# Pure_SH.net
KiCad netlist of a schematic drawn in EAGLE
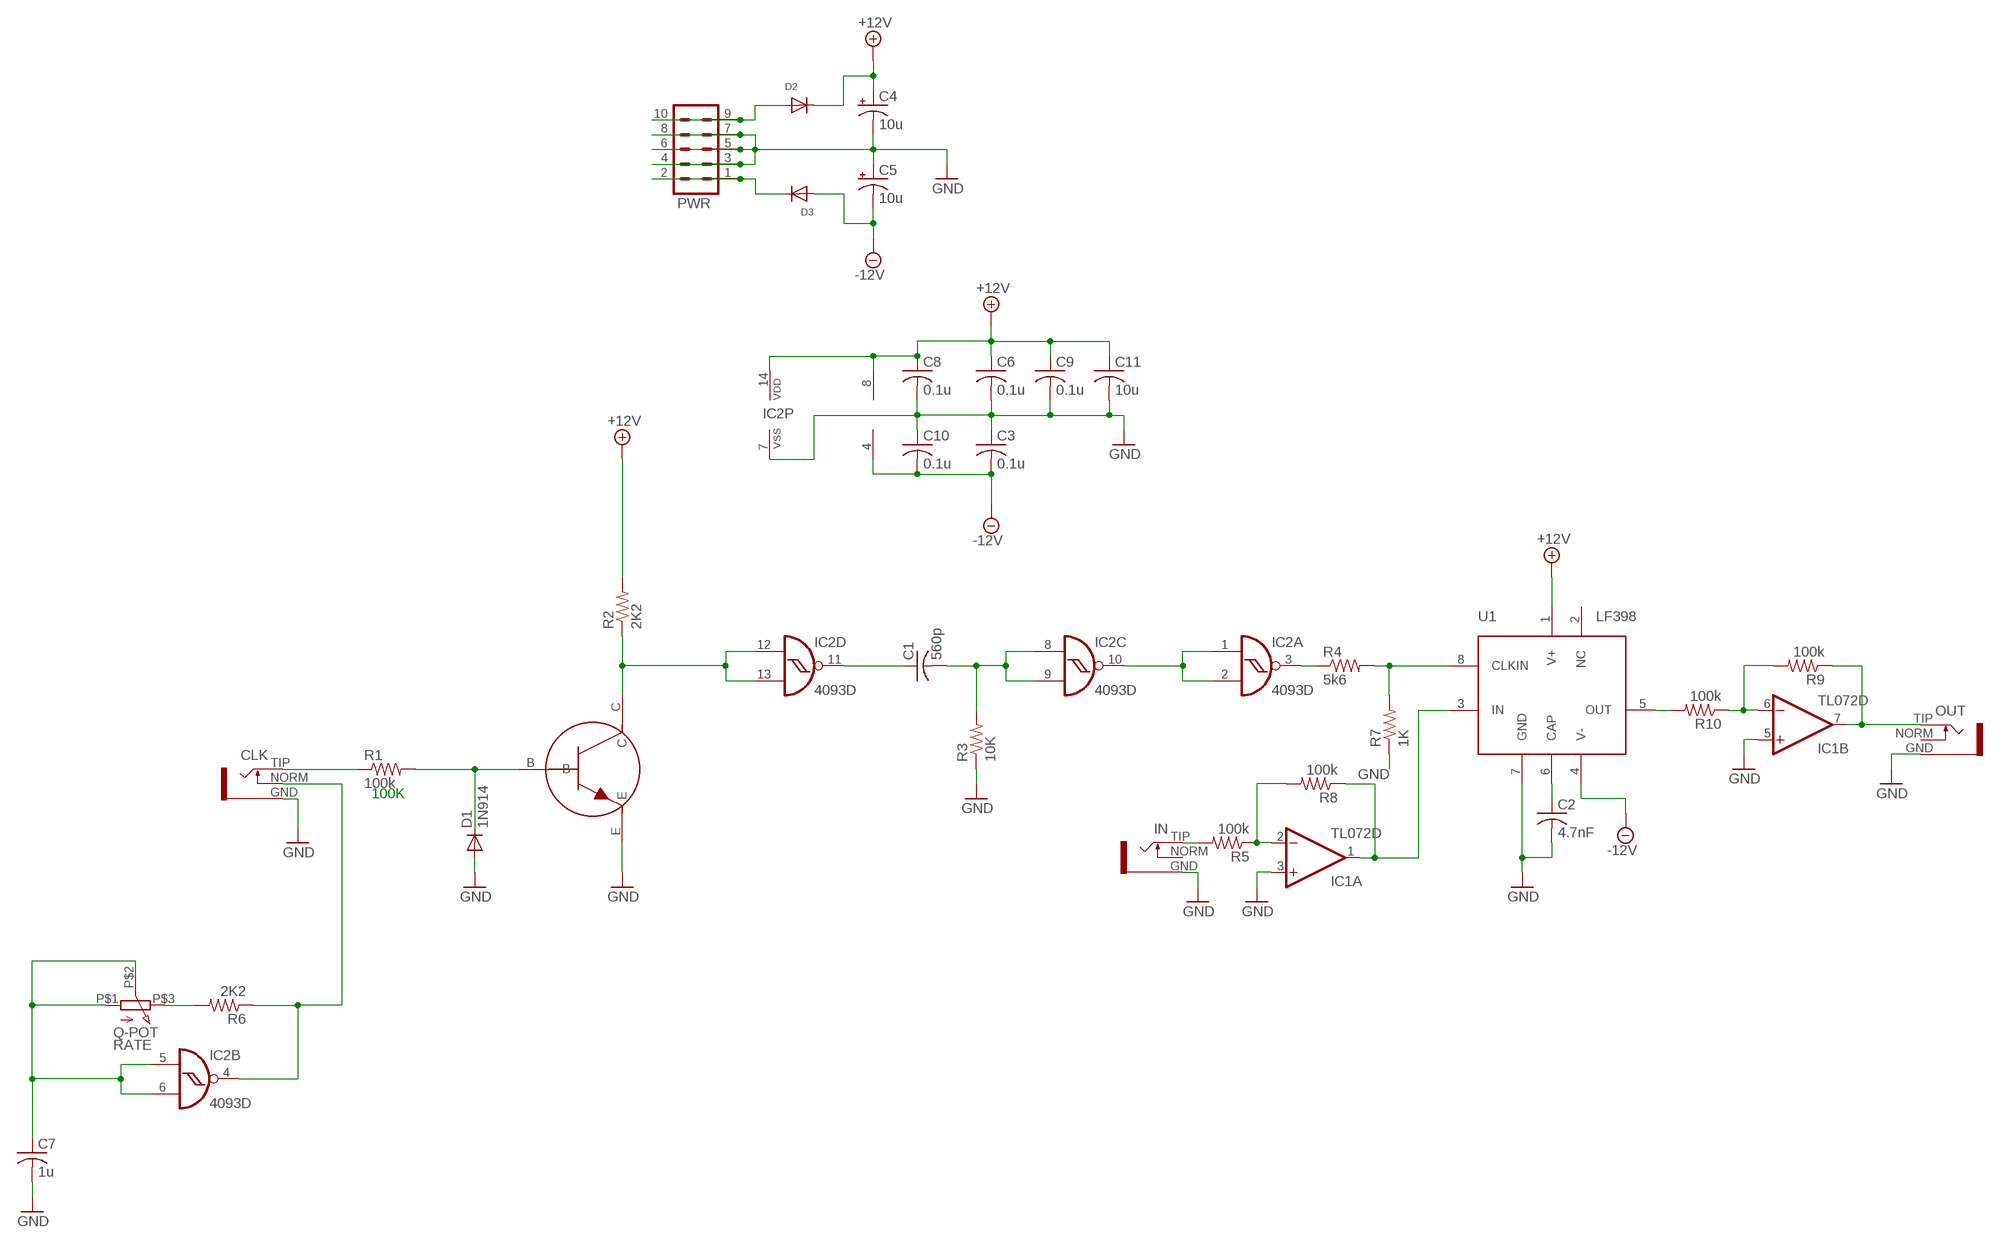
[diagram p0: schematic, sheet 1]

(export (version "E")
  (design (tool "Eeschema 10.0.6"))
  (components
    (comp (ref "C1")
      (value "560p")
      (footprint "eagle-import:C0805K")
      (libsource (lib "eagle-import") (part "C-USC0805K"))
    )
    (comp (ref "C2")
      (value "4.7nF")
      (footprint "eagle-import:C050-045X075")
      (libsource (lib "eagle-import") (part "C-US050-045X075"))
    )
    (comp (ref "C3")
      (value "0.1u")
      (footprint "eagle-import:C0805K")
      (libsource (lib "eagle-import") (part "C-USC0805K"))
    )
    (comp (ref "C4")
      (value "10u")
      (footprint "eagle-import:153CLV-0505")
      (libsource (lib "eagle-import") (part "CPOL-US153CLV-0505"))
    )
    (comp (ref "C5")
      (value "10u")
      (footprint "eagle-import:153CLV-0505")
      (libsource (lib "eagle-import") (part "CPOL-US153CLV-0505"))
    )
    (comp (ref "C6")
      (value "0.1u")
      (footprint "eagle-import:C0805K")
      (libsource (lib "eagle-import") (part "C-USC0805K"))
    )
    (comp (ref "C7")
      (value "1u")
      (footprint "eagle-import:C0805K")
      (libsource (lib "eagle-import") (part "C-USC0805K"))
    )
    (comp (ref "C8")
      (value "0.1u")
      (footprint "eagle-import:C0805K")
      (libsource (lib "eagle-import") (part "C-USC0805K"))
    )
    (comp (ref "C9")
      (value "0.1u")
      (footprint "eagle-import:C0805K")
      (libsource (lib "eagle-import") (part "C-USC0805K"))
    )
    (comp (ref "C10")
      (value "0.1u")
      (footprint "eagle-import:C0805K")
      (libsource (lib "eagle-import") (part "C-USC0805K"))
    )
    (comp (ref "C11")
      (value "10u")
      (footprint "eagle-import:C0805K")
      (libsource (lib "eagle-import") (part "C-USC0805K"))
    )
    (comp (ref "CLK")
      (value "S_JACK")
      (footprint "eagle-import:S_JACK")
      (libsource (lib "eagle-import") (part "S_JACK"))
    )
    (comp (ref "D1")
      (value "1N914")
      (footprint "eagle-import:SOD-323")
      (libsource (lib "eagle-import") (part "DIODESOD"))
    )
    (comp (ref "D2")
      (value "DIODESMA")
      (footprint "eagle-import:SMADIODE")
      (libsource (lib "eagle-import") (part "adafruit_DIODESMA"))
    )
    (comp (ref "D3")
      (value "DIODESMA")
      (footprint "eagle-import:SMADIODE")
      (libsource (lib "eagle-import") (part "adafruit_DIODESMA"))
    )
    (comp (ref "IC1")
      (value "TL072D")
      (footprint "eagle-import:SO08")
      (libsource (lib "eagle-import") (part "TL072D"))
    )
    (comp (ref "IC2")
      (value "4093D")
      (footprint "eagle-import:SO14")
      (libsource (lib "eagle-import") (part "4093D"))
    )
    (comp (ref "IN")
      (value "S_JACK")
      (footprint "eagle-import:S_JACK")
      (libsource (lib "eagle-import") (part "S_JACK"))
    )
    (comp (ref "OUT")
      (value "S_JACK")
      (footprint "eagle-import:S_JACK")
      (libsource (lib "eagle-import") (part "S_JACK"))
    )
    (comp (ref "PWR")
      (value "M05X2SHD")
      (footprint "eagle-import:2X5-SHROUDED")
      (libsource (lib "eagle-import") (part "M05X2SHD"))
    )
    (comp (ref "R1")
      (value "100k")
      (footprint "eagle-import:R0805")
      (libsource (lib "eagle-import") (part "R-US_R0805"))
    )
    (comp (ref "R2")
      (value "2K2")
      (footprint "eagle-import:R0805")
      (libsource (lib "eagle-import") (part "R-US_R0805"))
    )
    (comp (ref "R3")
      (value "10K")
      (footprint "eagle-import:R0805")
      (libsource (lib "eagle-import") (part "R-US_R0805"))
    )
    (comp (ref "R4")
      (value "5k6")
      (footprint "eagle-import:R0805")
      (libsource (lib "eagle-import") (part "R-US_R0805"))
    )
    (comp (ref "R5")
      (value "100k")
      (footprint "eagle-import:R0805")
      (libsource (lib "eagle-import") (part "R-US_R0805"))
    )
    (comp (ref "R6")
      (value "2K2")
      (footprint "eagle-import:R0805")
      (libsource (lib "eagle-import") (part "R-US_R0805"))
    )
    (comp (ref "R7")
      (value "1K")
      (footprint "eagle-import:R0805")
      (libsource (lib "eagle-import") (part "R-US_R0805"))
    )
    (comp (ref "R8")
      (value "100k")
      (footprint "eagle-import:R0805")
      (libsource (lib "eagle-import") (part "R-US_R0805"))
    )
    (comp (ref "R9")
      (value "100k")
      (footprint "eagle-import:R0805")
      (libsource (lib "eagle-import") (part "R-US_R0805"))
    )
    (comp (ref "R10")
      (value "100k")
      (footprint "eagle-import:R0805")
      (libsource (lib "eagle-import") (part "R-US_R0805"))
    )
    (comp (ref "RATE")
      (value "Q-POT")
      (footprint "eagle-import:Q-POT")
      (libsource (lib "eagle-import") (part "Q-POT"))
    )
    (comp (ref "T1")
      (value "3904")
      (footprint "eagle-import:TRANSISTOR_SINGLE_N-TYPE")
      (libsource (lib "eagle-import") (part "TRANSISTOR_MMBT3904"))
    )
    (comp (ref "U1")
      (value "LF398")
      (footprint "eagle-import:SOIC--8")
      (libsource (lib "eagle-import") (part "LF398"))
    )
  )
  (nets
    (net (code "1") (name "+12V") (class "Default")
      (node (ref "C11") (pin "1") (pinfunction "1_1") (pintype "passive"))
      (node (ref "C4") (pin "+") (pinfunction "+_+") (pintype "passive"))
      (node (ref "C6") (pin "1") (pinfunction "1_1") (pintype "passive"))
      (node (ref "C8") (pin "1") (pinfunction "1_1") (pintype "passive"))
      (node (ref "C9") (pin "1") (pinfunction "1_1") (pintype "passive"))
      (node (ref "D2") (pin "C") (pinfunction "C_C") (pintype "passive"))
      (node (ref "IC1") (pin "8") (pinfunction "V+_8") (pintype "power_in"))
      (node (ref "IC2") (pin "14") (pinfunction "VDD_14") (pintype "power_in"))
      (node (ref "R2") (pin "2") (pinfunction "2_2") (pintype "passive"))
      (node (ref "U1") (pin "1") (pinfunction "V+_1") (pintype "bidirectional"))
    )
    (net (code "2") (name "-12V") (class "Default")
      (node (ref "C10") (pin "2") (pinfunction "2_2") (pintype "passive"))
      (node (ref "C3") (pin "2") (pinfunction "2_2") (pintype "passive"))
      (node (ref "C5") (pin "-") (pinfunction "-_-") (pintype "passive"))
      (node (ref "D3") (pin "A") (pinfunction "A_A") (pintype "passive"))
      (node (ref "IC1") (pin "4") (pinfunction "V-_4") (pintype "power_in"))
      (node (ref "U1") (pin "4") (pinfunction "V-_4") (pintype "bidirectional"))
    )
    (net (code "3") (name "GND") (class "Default")
      (node (ref "C10") (pin "1") (pinfunction "1_1") (pintype "passive"))
      (node (ref "C11") (pin "2") (pinfunction "2_2") (pintype "passive"))
      (node (ref "C2") (pin "2") (pinfunction "2_2") (pintype "passive"))
      (node (ref "C3") (pin "1") (pinfunction "1_1") (pintype "passive"))
      (node (ref "C4") (pin "-") (pinfunction "-_-") (pintype "passive"))
      (node (ref "C5") (pin "+") (pinfunction "+_+") (pintype "passive"))
      (node (ref "C6") (pin "2") (pinfunction "2_2") (pintype "passive"))
      (node (ref "C7") (pin "2") (pinfunction "2_2") (pintype "passive"))
      (node (ref "C8") (pin "2") (pinfunction "2_2") (pintype "passive"))
      (node (ref "C9") (pin "2") (pinfunction "2_2") (pintype "passive"))
      (node (ref "CLK") (pin "GND") (pinfunction "GND_GND") (pintype "passive"))
      (node (ref "D1") (pin "2") (pinfunction "A_2") (pintype "passive"))
      (node (ref "IC1") (pin "3") (pinfunction "+IN_3") (pintype "input"))
      (node (ref "IC1") (pin "5") (pinfunction "+IN_5") (pintype "input"))
      (node (ref "IC2") (pin "7") (pinfunction "VSS_7") (pintype "power_in"))
      (node (ref "IN") (pin "GND") (pinfunction "GND_GND") (pintype "passive"))
      (node (ref "OUT") (pin "GND") (pinfunction "GND_GND") (pintype "passive"))
      (node (ref "PWR") (pin "3") (pinfunction "3_3") (pintype "passive"))
      (node (ref "PWR") (pin "4") (pinfunction "4_4") (pintype "passive"))
      (node (ref "PWR") (pin "5") (pinfunction "5_5") (pintype "passive"))
      (node (ref "PWR") (pin "6") (pinfunction "6_6") (pintype "passive"))
      (node (ref "PWR") (pin "7") (pinfunction "7_7") (pintype "passive"))
      (node (ref "PWR") (pin "8") (pinfunction "8_8") (pintype "passive"))
      (node (ref "R3") (pin "1") (pinfunction "1_1") (pintype "passive"))
      (node (ref "R7") (pin "1") (pinfunction "1_1") (pintype "passive"))
      (node (ref "T1") (pin "E") (pinfunction "E_E") (pintype "bidirectional"))
      (node (ref "U1") (pin "7") (pinfunction "GND_7") (pintype "bidirectional"))
    )
    (net (code "4") (name "Net-(CLK-PadTIP)") (class "Default")
      (node (ref "CLK") (pin "TIP") (pinfunction "TIP_TIP") (pintype "passive"))
      (node (ref "R1") (pin "1") (pinfunction "1_1") (pintype "passive"))
    )
    (net (code "5") (name "Net-(D1-C)") (class "Default")
      (node (ref "D1") (pin "1") (pinfunction "C_1") (pintype "passive"))
      (node (ref "R1") (pin "2") (pinfunction "2_2") (pintype "passive"))
      (node (ref "T1") (pin "B") (pinfunction "B_B") (pintype "bidirectional"))
    )
    (net (code "6") (name "Net-(D2-PadA)") (class "Default")
      (node (ref "D2") (pin "A") (pinfunction "A_A") (pintype "passive"))
      (node (ref "PWR") (pin "10") (pinfunction "10_10") (pintype "passive"))
      (node (ref "PWR") (pin "9") (pinfunction "9_9") (pintype "passive"))
    )
    (net (code "7") (name "Net-(D3-PadC)") (class "Default")
      (node (ref "D3") (pin "C") (pinfunction "C_C") (pintype "passive"))
      (node (ref "PWR") (pin "1") (pinfunction "1_1") (pintype "passive"))
      (node (ref "PWR") (pin "2") (pinfunction "2_2") (pintype "passive"))
    )
    (net (code "8") (name "Net-(IC1A--IN)") (class "Default")
      (node (ref "IC1") (pin "2") (pinfunction "-IN_2") (pintype "input"))
      (node (ref "R5") (pin "1") (pinfunction "1_1") (pintype "passive"))
      (node (ref "R8") (pin "2") (pinfunction "2_2") (pintype "passive"))
    )
    (net (code "9") (name "Net-(IC1A-OUT)") (class "Default")
      (node (ref "IC1") (pin "1") (pinfunction "OUT_1") (pintype "output"))
      (node (ref "R8") (pin "1") (pinfunction "1_1") (pintype "passive"))
      (node (ref "U1") (pin "3") (pinfunction "IN_3") (pintype "bidirectional"))
    )
    (net (code "10") (name "Net-(IC1B--IN)") (class "Default")
      (node (ref "IC1") (pin "6") (pinfunction "-IN_6") (pintype "input"))
      (node (ref "R10") (pin "1") (pinfunction "1_1") (pintype "passive"))
      (node (ref "R9") (pin "2") (pinfunction "2_2") (pintype "passive"))
    )
    (net (code "11") (name "Net-(IC1B-OUT)") (class "Default")
      (node (ref "IC1") (pin "7") (pinfunction "OUT_7") (pintype "output"))
      (node (ref "OUT") (pin "TIP") (pinfunction "TIP_TIP") (pintype "passive"))
      (node (ref "R9") (pin "1") (pinfunction "1_1") (pintype "passive"))
    )
    (net (code "12") (name "Net-(IC2A-I0)") (class "Default")
      (node (ref "IC2") (pin "1") (pinfunction "I0_1") (pintype "input"))
      (node (ref "IC2") (pin "10") (pinfunction "O_10") (pintype "output"))
      (node (ref "IC2") (pin "2") (pinfunction "I1_2") (pintype "input"))
    )
    (net (code "13") (name "Net-(IC2A-O)") (class "Default")
      (node (ref "IC2") (pin "3") (pinfunction "O_3") (pintype "output"))
      (node (ref "R4") (pin "1") (pinfunction "1_1") (pintype "passive"))
    )
    (net (code "14") (name "Net-(IC2B-I0)") (class "Default")
      (node (ref "C7") (pin "1") (pinfunction "1_1") (pintype "passive"))
      (node (ref "IC2") (pin "5") (pinfunction "I0_5") (pintype "input"))
      (node (ref "IC2") (pin "6") (pinfunction "I1_6") (pintype "input"))
      (node (ref "RATE") (pin "P$1") (pinfunction "1_P$1") (pintype "passive"))
      (node (ref "RATE") (pin "P$2") (pinfunction "2_P$2") (pintype "passive"))
    )
    (net (code "15") (name "Net-(IC2B-O)") (class "Default")
      (node (ref "CLK") (pin "NORM") (pinfunction "NORM_NORM") (pintype "passive"))
      (node (ref "IC2") (pin "4") (pinfunction "O_4") (pintype "output"))
      (node (ref "R6") (pin "1") (pinfunction "1_1") (pintype "passive"))
    )
    (net (code "16") (name "Net-(IC2C-I0)") (class "Default")
      (node (ref "C1") (pin "2") (pinfunction "2_2") (pintype "passive"))
      (node (ref "IC2") (pin "8") (pinfunction "I0_8") (pintype "input"))
      (node (ref "IC2") (pin "9") (pinfunction "I1_9") (pintype "input"))
      (node (ref "R3") (pin "2") (pinfunction "2_2") (pintype "passive"))
    )
    (net (code "17") (name "Net-(IC2D-I0)") (class "Default")
      (node (ref "IC2") (pin "12") (pinfunction "I0_12") (pintype "input"))
      (node (ref "IC2") (pin "13") (pinfunction "I1_13") (pintype "input"))
      (node (ref "R2") (pin "1") (pinfunction "1_1") (pintype "passive"))
      (node (ref "T1") (pin "C") (pinfunction "C_C") (pintype "bidirectional"))
    )
    (net (code "18") (name "Net-(IC2D-O)") (class "Default")
      (node (ref "C1") (pin "1") (pinfunction "1_1") (pintype "passive"))
      (node (ref "IC2") (pin "11") (pinfunction "O_11") (pintype "output"))
    )
    (net (code "19") (name "Net-(IN-PadTIP)") (class "Default")
      (node (ref "IN") (pin "TIP") (pinfunction "TIP_TIP") (pintype "passive"))
      (node (ref "R5") (pin "2") (pinfunction "2_2") (pintype "passive"))
    )
    (net (code "20") (name "Net-(RATE-3)") (class "Default")
      (node (ref "R6") (pin "2") (pinfunction "2_2") (pintype "passive"))
      (node (ref "RATE") (pin "P$3") (pinfunction "3_P$3") (pintype "passive"))
    )
    (net (code "21") (name "Net-(U1-CAP)") (class "Default")
      (node (ref "C2") (pin "1") (pinfunction "1_1") (pintype "passive"))
      (node (ref "U1") (pin "6") (pinfunction "CAP_6") (pintype "bidirectional"))
    )
    (net (code "22") (name "Net-(U1-CLKIN)") (class "Default")
      (node (ref "R4") (pin "2") (pinfunction "2_2") (pintype "passive"))
      (node (ref "R7") (pin "2") (pinfunction "2_2") (pintype "passive"))
      (node (ref "U1") (pin "8") (pinfunction "CLKIN_8") (pintype "bidirectional"))
    )
    (net (code "23") (name "Net-(U1-OUT)") (class "Default")
      (node (ref "R10") (pin "2") (pinfunction "2_2") (pintype "passive"))
      (node (ref "U1") (pin "5") (pinfunction "OUT_5") (pintype "bidirectional"))
    )
    (net (code "24") (name "unconnected-(IN-PadNORM)") (class "Default")
      (node (ref "IN") (pin "NORM") (pinfunction "NORM_NORM") (pintype "passive"))
    )
    (net (code "25") (name "unconnected-(OUT-PadNORM)") (class "Default")
      (node (ref "OUT") (pin "NORM") (pinfunction "NORM_NORM") (pintype "passive"))
    )
    (net (code "26") (name "unconnected-(U1-NC-Pad2)") (class "Default")
      (node (ref "U1") (pin "2") (pinfunction "NC_2") (pintype "bidirectional"))
    )
  )
)
